# 05-Front_Panel_SFP.net
KiCad netlist of a schematic drawn in Altium Designer
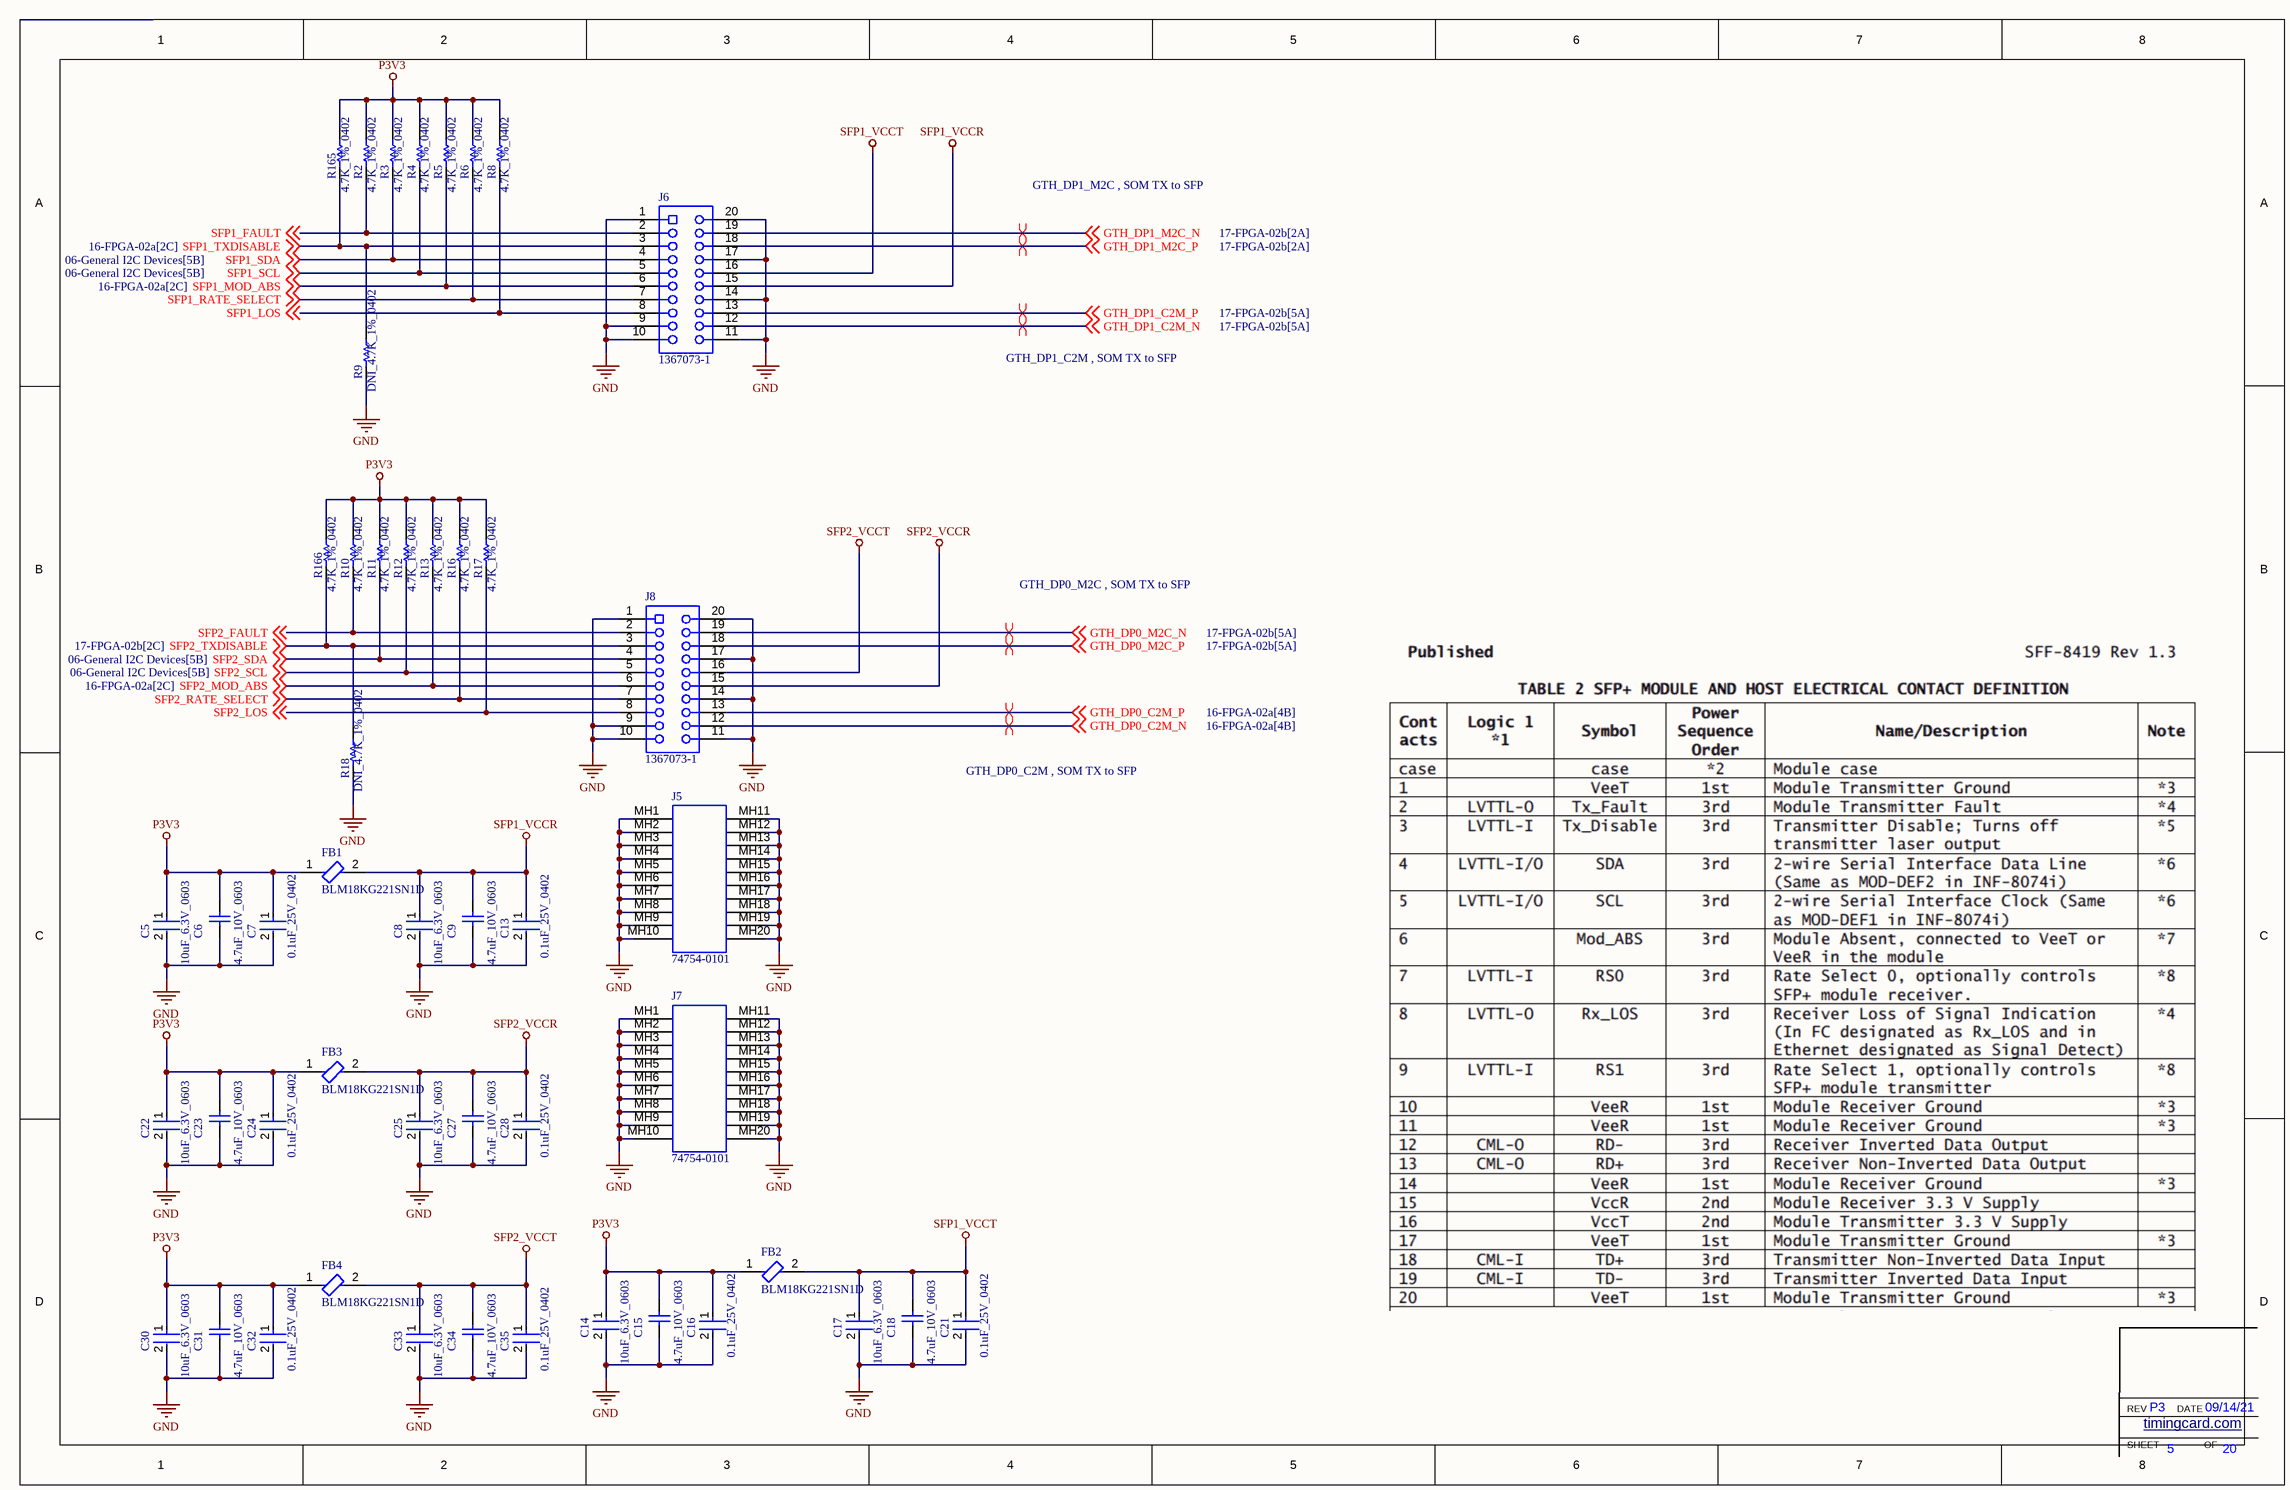
[diagram p0: 05-Front Panel SFP+.SchDoc]

(export (version "E")
  (design (tool "Eeschema 10.0.6"))
  (components
    (comp (ref "C5")
      (value "10uF_6.3V_0603")
      (footprint "FP-C0603C106M9PACTU-MFG")
      (description "CAP CER 10UF 6.3V X5R 0603")
      (fields
        (field (name "MANUFACTURER PART NUMBER") "C0603C106M9PACTU")
        (field (name "MANUFACTURER") "Kemet")
      )
      (libsource (lib "Altium Content Vault") (part "b4654b650e69147ec39a6b967a45e02"))
    )
    (comp (ref "C6")
      (value "4.7uF_10V_0603")
      (footprint "CAPC1608X87X35NL15T15")
      (fields (field (name "PART NUMBER") "C0603C475K8PACTU") (field (name "MANUFACTURER") "Kemet"))
      (libsource (lib "Altium Content Vault") (part "CAP"))
    )
    (comp (ref "C7")
      (value "0.1uF_25V_0402")
      (footprint "FP-0402-L_1_0_1-W_0_5_0_1-IPC_C")
      (description "General Purpose Ceramic Capacitor, 0402, 100nF, 10%, X7R, 15%, 25V")
      (fields (field (name "VOLTAGE") "25V") (field (name "TOLERANCE") "10%"))
      (libsource (lib "Altium Content Vault") (part "b4654b650e69147ec39a6b967a45e02"))
    )
    (comp (ref "C8")
      (value "10uF_6.3V_0603")
      (footprint "FP-C0603C106M9PACTU-MFG")
      (description "CAP CER 10UF 6.3V X5R 0603")
      (fields
        (field (name "MANUFACTURER PART NUMBER") "C0603C106M9PACTU")
        (field (name "MANUFACTURER") "Kemet")
      )
      (libsource (lib "Altium Content Vault") (part "b4654b650e69147ec39a6b967a45e02"))
    )
    (comp (ref "C9")
      (value "4.7uF_10V_0603")
      (footprint "CAPC1608X87X35NL15T15")
      (fields (field (name "PART NUMBER") "C0603C475K8PACTU") (field (name "MANUFACTURER") "Kemet"))
      (libsource (lib "Altium Content Vault") (part "CAP"))
    )
    (comp (ref "C13")
      (value "0.1uF_25V_0402")
      (footprint "FP-0402-L_1_0_1-W_0_5_0_1-IPC_C")
      (description "General Purpose Ceramic Capacitor, 0402, 100nF, 10%, X7R, 15%, 25V")
      (fields (field (name "VOLTAGE") "25V") (field (name "TOLERANCE") "10%"))
      (libsource (lib "Altium Content Vault") (part "b4654b650e69147ec39a6b967a45e02"))
    )
    (comp (ref "C14")
      (value "10uF_6.3V_0603")
      (footprint "FP-C0603C106M9PACTU-MFG")
      (description "CAP CER 10UF 6.3V X5R 0603")
      (fields
        (field (name "MANUFACTURER PART NUMBER") "C0603C106M9PACTU")
        (field (name "MANUFACTURER") "Kemet")
      )
      (libsource (lib "Altium Content Vault") (part "b4654b650e69147ec39a6b967a45e02"))
    )
    (comp (ref "C15")
      (value "4.7uF_10V_0603")
      (footprint "CAPC1608X87X35NL15T15")
      (fields (field (name "PART NUMBER") "C0603C475K8PACTU") (field (name "MANUFACTURER") "Kemet"))
      (libsource (lib "Altium Content Vault") (part "CAP"))
    )
    (comp (ref "C16")
      (value "0.1uF_25V_0402")
      (footprint "FP-0402-L_1_0_1-W_0_5_0_1-IPC_C")
      (description "General Purpose Ceramic Capacitor, 0402, 100nF, 10%, X7R, 15%, 25V")
      (fields (field (name "VOLTAGE") "25V") (field (name "TOLERANCE") "10%"))
      (libsource (lib "Altium Content Vault") (part "b4654b650e69147ec39a6b967a45e02"))
    )
    (comp (ref "C17")
      (value "10uF_6.3V_0603")
      (footprint "FP-C0603C106M9PACTU-MFG")
      (description "CAP CER 10UF 6.3V X5R 0603")
      (fields
        (field (name "MANUFACTURER PART NUMBER") "C0603C106M9PACTU")
        (field (name "MANUFACTURER") "Kemet")
      )
      (libsource (lib "Altium Content Vault") (part "b4654b650e69147ec39a6b967a45e02"))
    )
    (comp (ref "C18")
      (value "4.7uF_10V_0603")
      (footprint "CAPC1608X87X35NL15T15")
      (fields (field (name "PART NUMBER") "C0603C475K8PACTU") (field (name "MANUFACTURER") "Kemet"))
      (libsource (lib "Altium Content Vault") (part "CAP"))
    )
    (comp (ref "C21")
      (value "0.1uF_25V_0402")
      (footprint "FP-0402-L_1_0_1-W_0_5_0_1-IPC_C")
      (description "General Purpose Ceramic Capacitor, 0402, 100nF, 10%, X7R, 15%, 25V")
      (fields (field (name "VOLTAGE") "25V") (field (name "TOLERANCE") "10%"))
      (libsource (lib "Altium Content Vault") (part "b4654b650e69147ec39a6b967a45e02"))
    )
    (comp (ref "C22")
      (value "10uF_6.3V_0603")
      (footprint "FP-C0603C106M9PACTU-MFG")
      (description "CAP CER 10UF 6.3V X5R 0603")
      (fields
        (field (name "MANUFACTURER PART NUMBER") "C0603C106M9PACTU")
        (field (name "MANUFACTURER") "Kemet")
      )
      (libsource (lib "Altium Content Vault") (part "b4654b650e69147ec39a6b967a45e02"))
    )
    (comp (ref "C23")
      (value "4.7uF_10V_0603")
      (footprint "CAPC1608X87X35NL15T15")
      (fields (field (name "PART NUMBER") "C0603C475K8PACTU") (field (name "MANUFACTURER") "Kemet"))
      (libsource (lib "Altium Content Vault") (part "CAP"))
    )
    (comp (ref "C24")
      (value "0.1uF_25V_0402")
      (footprint "FP-0402-L_1_0_1-W_0_5_0_1-IPC_C")
      (description "General Purpose Ceramic Capacitor, 0402, 100nF, 10%, X7R, 15%, 25V")
      (fields (field (name "VOLTAGE") "25V") (field (name "TOLERANCE") "10%"))
      (libsource (lib "Altium Content Vault") (part "b4654b650e69147ec39a6b967a45e02"))
    )
    (comp (ref "C25")
      (value "10uF_6.3V_0603")
      (footprint "FP-C0603C106M9PACTU-MFG")
      (description "CAP CER 10UF 6.3V X5R 0603")
      (fields
        (field (name "MANUFACTURER PART NUMBER") "C0603C106M9PACTU")
        (field (name "MANUFACTURER") "Kemet")
      )
      (libsource (lib "Altium Content Vault") (part "b4654b650e69147ec39a6b967a45e02"))
    )
    (comp (ref "C27")
      (value "4.7uF_10V_0603")
      (footprint "CAPC1608X87X35NL15T15")
      (fields (field (name "PART NUMBER") "C0603C475K8PACTU") (field (name "MANUFACTURER") "Kemet"))
      (libsource (lib "Altium Content Vault") (part "CAP"))
    )
    (comp (ref "C28")
      (value "0.1uF_25V_0402")
      (footprint "FP-0402-L_1_0_1-W_0_5_0_1-IPC_C")
      (description "General Purpose Ceramic Capacitor, 0402, 100nF, 10%, X7R, 15%, 25V")
      (fields (field (name "VOLTAGE") "25V") (field (name "TOLERANCE") "10%"))
      (libsource (lib "Altium Content Vault") (part "b4654b650e69147ec39a6b967a45e02"))
    )
    (comp (ref "C30")
      (value "10uF_6.3V_0603")
      (footprint "FP-C0603C106M9PACTU-MFG")
      (description "CAP CER 10UF 6.3V X5R 0603")
      (fields
        (field (name "MANUFACTURER PART NUMBER") "C0603C106M9PACTU")
        (field (name "MANUFACTURER") "Kemet")
      )
      (libsource (lib "Altium Content Vault") (part "b4654b650e69147ec39a6b967a45e02"))
    )
    (comp (ref "C31")
      (value "4.7uF_10V_0603")
      (footprint "CAPC1608X87X35NL15T15")
      (fields (field (name "PART NUMBER") "C0603C475K8PACTU") (field (name "MANUFACTURER") "Kemet"))
      (libsource (lib "Altium Content Vault") (part "CAP"))
    )
    (comp (ref "C32")
      (value "0.1uF_25V_0402")
      (footprint "FP-0402-L_1_0_1-W_0_5_0_1-IPC_C")
      (description "General Purpose Ceramic Capacitor, 0402, 100nF, 10%, X7R, 15%, 25V")
      (fields (field (name "VOLTAGE") "25V") (field (name "TOLERANCE") "10%"))
      (libsource (lib "Altium Content Vault") (part "b4654b650e69147ec39a6b967a45e02"))
    )
    (comp (ref "C33")
      (value "10uF_6.3V_0603")
      (footprint "FP-C0603C106M9PACTU-MFG")
      (description "CAP CER 10UF 6.3V X5R 0603")
      (fields
        (field (name "MANUFACTURER PART NUMBER") "C0603C106M9PACTU")
        (field (name "MANUFACTURER") "Kemet")
      )
      (libsource (lib "Altium Content Vault") (part "b4654b650e69147ec39a6b967a45e02"))
    )
    (comp (ref "C34")
      (value "4.7uF_10V_0603")
      (footprint "CAPC1608X87X35NL15T15")
      (fields (field (name "PART NUMBER") "C0603C475K8PACTU") (field (name "MANUFACTURER") "Kemet"))
      (libsource (lib "Altium Content Vault") (part "CAP"))
    )
    (comp (ref "C35")
      (value "0.1uF_25V_0402")
      (footprint "FP-0402-L_1_0_1-W_0_5_0_1-IPC_C")
      (description "General Purpose Ceramic Capacitor, 0402, 100nF, 10%, X7R, 15%, 25V")
      (fields (field (name "VOLTAGE") "25V") (field (name "TOLERANCE") "10%"))
      (libsource (lib "Altium Content Vault") (part "b4654b650e69147ec39a6b967a45e02"))
    )
    (comp (ref "FB1")
      (value "BLM18KG221SN1D")
      (footprint "FP-BLM18-0_15-t0_8-IPC_B")
      (description "Chip Ferrite Bead, 0603, 220Ω @ 100MHz, 0.05Ω, 25%, 2.2A")
      (fields (field (name "TOLERANCE") "25%"))
      (libsource (lib "Altium Content Vault") (part "5f30dd21d616792df468990f7003faa"))
    )
    (comp (ref "FB2")
      (value "BLM18KG221SN1D")
      (footprint "FP-BLM18-0_15-t0_8-IPC_B")
      (description "Chip Ferrite Bead, 0603, 220Ω @ 100MHz, 0.05Ω, 25%, 2.2A")
      (fields (field (name "TOLERANCE") "25%"))
      (libsource (lib "Altium Content Vault") (part "5f30dd21d616792df468990f7003faa"))
    )
    (comp (ref "FB3")
      (value "BLM18KG221SN1D")
      (footprint "FP-BLM18-0_15-t0_8-IPC_B")
      (description "Chip Ferrite Bead, 0603, 220Ω @ 100MHz, 0.05Ω, 25%, 2.2A")
      (fields (field (name "TOLERANCE") "25%"))
      (libsource (lib "Altium Content Vault") (part "5f30dd21d616792df468990f7003faa"))
    )
    (comp (ref "FB4")
      (value "BLM18KG221SN1D")
      (footprint "FP-BLM18-0_15-t0_8-IPC_B")
      (description "Chip Ferrite Bead, 0603, 220Ω @ 100MHz, 0.05Ω, 25%, 2.2A")
      (fields (field (name "TOLERANCE") "25%"))
      (libsource (lib "Altium Content Vault") (part "5f30dd21d616792df468990f7003faa"))
    )
    (comp (ref "J5")
      (value "74754-0101")
      (footprint "MOLX-74754-0101_V")
      (description "SFP+ Cage, Single Port, Height 10.85 mm, Tail Height 3.05 mm, -40 to 85 degC, RoHS, Tray")
      (libsource (lib "Altium Content Vault") (part "MOLX-74754-0101"))
    )
    (comp (ref "J6")
      (value "1367073-1")
      (footprint "TECO-1367073-1_V")
      (fields (field (name "MANUFACTURER") "TE Connectivity"))
      (libsource (lib "Altium Content Vault") (part "CN-2P-F-R20_B"))
    )
    (comp (ref "J7")
      (value "74754-0101")
      (footprint "MOLX-74754-0101_V")
      (description "SFP+ Cage, Single Port, Height 10.85 mm, Tail Height 3.05 mm, -40 to 85 degC, RoHS, Tray")
      (libsource (lib "Altium Content Vault") (part "MOLX-74754-0101"))
    )
    (comp (ref "J8")
      (value "1367073-1")
      (footprint "TECO-1367073-1_V")
      (fields (field (name "MANUFACTURER") "TE Connectivity"))
      (libsource (lib "Altium Content Vault") (part "CN-2P-F-R20_B"))
    )
    (comp (ref "R2")
      (value "4.7K_1%_0402")
      (footprint "RESC1005X40X25NL10T10")
      (fields (field (name "MANUFACTURER") "Bourns") (field (name "PART NUMBER") "CR0402-FX-4701GLF"))
      (libsource (lib "Altium Content Vault") (part "RES"))
    )
    (comp (ref "R3")
      (value "4.7K_1%_0402")
      (footprint "RESC1005X40X25NL10T10")
      (fields (field (name "MANUFACTURER") "Bourns") (field (name "PART NUMBER") "CR0402-FX-4701GLF"))
      (libsource (lib "Altium Content Vault") (part "RES"))
    )
    (comp (ref "R4")
      (value "4.7K_1%_0402")
      (footprint "RESC1005X40X25NL10T10")
      (fields (field (name "MANUFACTURER") "Bourns") (field (name "PART NUMBER") "CR0402-FX-4701GLF"))
      (libsource (lib "Altium Content Vault") (part "RES"))
    )
    (comp (ref "R5")
      (value "4.7K_1%_0402")
      (footprint "RESC1005X40X25NL10T10")
      (fields (field (name "MANUFACTURER") "Bourns") (field (name "PART NUMBER") "CR0402-FX-4701GLF"))
      (libsource (lib "Altium Content Vault") (part "RES"))
    )
    (comp (ref "R6")
      (value "4.7K_1%_0402")
      (footprint "RESC1005X40X25NL10T10")
      (fields (field (name "MANUFACTURER") "Bourns") (field (name "PART NUMBER") "CR0402-FX-4701GLF"))
      (libsource (lib "Altium Content Vault") (part "RES"))
    )
    (comp (ref "R8")
      (value "4.7K_1%_0402")
      (footprint "RESC1005X40X25NL10T10")
      (fields (field (name "MANUFACTURER") "Bourns") (field (name "PART NUMBER") "CR0402-FX-4701GLF"))
      (libsource (lib "Altium Content Vault") (part "RES"))
    )
    (comp (ref "R9")
      (value "DNI_4.7K_1%_0402")
      (footprint "RESC1005X40X25NL10T10")
      (fields (field (name "MANUFACTURER") "Bourns") (field (name "PART NUMBER") "CR0402-FX-4701GLF"))
      (libsource (lib "Altium Content Vault") (part "RES"))
    )
    (comp (ref "R10")
      (value "4.7K_1%_0402")
      (footprint "RESC1005X40X25NL10T10")
      (fields (field (name "MANUFACTURER") "Bourns") (field (name "PART NUMBER") "CR0402-FX-4701GLF"))
      (libsource (lib "Altium Content Vault") (part "RES"))
    )
    (comp (ref "R11")
      (value "4.7K_1%_0402")
      (footprint "RESC1005X40X25NL10T10")
      (fields (field (name "MANUFACTURER") "Bourns") (field (name "PART NUMBER") "CR0402-FX-4701GLF"))
      (libsource (lib "Altium Content Vault") (part "RES"))
    )
    (comp (ref "R12")
      (value "4.7K_1%_0402")
      (footprint "RESC1005X40X25NL10T10")
      (fields (field (name "MANUFACTURER") "Bourns") (field (name "PART NUMBER") "CR0402-FX-4701GLF"))
      (libsource (lib "Altium Content Vault") (part "RES"))
    )
    (comp (ref "R13")
      (value "4.7K_1%_0402")
      (footprint "RESC1005X40X25NL10T10")
      (fields (field (name "MANUFACTURER") "Bourns") (field (name "PART NUMBER") "CR0402-FX-4701GLF"))
      (libsource (lib "Altium Content Vault") (part "RES"))
    )
    (comp (ref "R16")
      (value "4.7K_1%_0402")
      (footprint "RESC1005X40X25NL10T10")
      (fields (field (name "MANUFACTURER") "Bourns") (field (name "PART NUMBER") "CR0402-FX-4701GLF"))
      (libsource (lib "Altium Content Vault") (part "RES"))
    )
    (comp (ref "R17")
      (value "4.7K_1%_0402")
      (footprint "RESC1005X40X25NL10T10")
      (fields (field (name "MANUFACTURER") "Bourns") (field (name "PART NUMBER") "CR0402-FX-4701GLF"))
      (libsource (lib "Altium Content Vault") (part "RES"))
    )
    (comp (ref "R18")
      (value "DNI_4.7K_1%_0402")
      (footprint "RESC1005X40X25NL10T10")
      (fields (field (name "MANUFACTURER") "Bourns") (field (name "PART NUMBER") "CR0402-FX-4701GLF"))
      (libsource (lib "Altium Content Vault") (part "RES"))
    )
    (comp (ref "R165")
      (value "4.7K_1%_0402")
      (footprint "RESC1005X40X25NL10T10")
      (fields (field (name "MANUFACTURER") "Bourns") (field (name "PART NUMBER") "CR0402-FX-4701GLF"))
      (libsource (lib "Altium Content Vault") (part "RES"))
    )
    (comp (ref "R166")
      (value "4.7K_1%_0402")
      (footprint "RESC1005X40X25NL10T10")
      (fields (field (name "MANUFACTURER") "Bourns") (field (name "PART NUMBER") "CR0402-FX-4701GLF"))
      (libsource (lib "Altium Content Vault") (part "RES"))
    )
  )
  (nets
    (net (code "1") (name "GND") (class "Default")
      (node (ref "C13") (pin "2") (pinfunction "2_2") (pintype "passive"))
      (node (ref "C14") (pin "2") (pinfunction "2_2") (pintype "passive"))
      (node (ref "C15") (pin "1") (pinfunction "1_1") (pintype "passive"))
      (node (ref "C16") (pin "2") (pinfunction "2_2") (pintype "passive"))
      (node (ref "C17") (pin "2") (pinfunction "2_2") (pintype "passive"))
      (node (ref "C18") (pin "1") (pinfunction "1_1") (pintype "passive"))
      (node (ref "C21") (pin "2") (pinfunction "2_2") (pintype "passive"))
      (node (ref "C22") (pin "2") (pinfunction "2_2") (pintype "passive"))
      (node (ref "C23") (pin "1") (pinfunction "1_1") (pintype "passive"))
      (node (ref "C24") (pin "2") (pinfunction "2_2") (pintype "passive"))
      (node (ref "C25") (pin "2") (pinfunction "2_2") (pintype "passive"))
      (node (ref "C27") (pin "1") (pinfunction "1_1") (pintype "passive"))
      (node (ref "C28") (pin "2") (pinfunction "2_2") (pintype "passive"))
      (node (ref "C30") (pin "2") (pinfunction "2_2") (pintype "passive"))
      (node (ref "C31") (pin "1") (pinfunction "1_1") (pintype "passive"))
      (node (ref "C32") (pin "2") (pinfunction "2_2") (pintype "passive"))
      (node (ref "C33") (pin "2") (pinfunction "2_2") (pintype "passive"))
      (node (ref "C34") (pin "1") (pinfunction "1_1") (pintype "passive"))
      (node (ref "C35") (pin "2") (pinfunction "2_2") (pintype "passive"))
      (node (ref "C5") (pin "2") (pinfunction "2_2") (pintype "passive"))
      (node (ref "C6") (pin "1") (pinfunction "1_1") (pintype "passive"))
      (node (ref "C7") (pin "2") (pinfunction "2_2") (pintype "passive"))
      (node (ref "C8") (pin "2") (pinfunction "2_2") (pintype "passive"))
      (node (ref "C9") (pin "1") (pinfunction "1_1") (pintype "passive"))
      (node (ref "J5") (pin "MH1") (pinfunction "MH1_MH1") (pintype "passive"))
      (node (ref "J5") (pin "MH10") (pinfunction "MH10_MH10") (pintype "passive"))
      (node (ref "J5") (pin "MH11") (pinfunction "MH11_MH11") (pintype "passive"))
      (node (ref "J5") (pin "MH12") (pinfunction "MH12_MH12") (pintype "passive"))
      (node (ref "J5") (pin "MH13") (pinfunction "MH13_MH13") (pintype "passive"))
      (node (ref "J5") (pin "MH14") (pinfunction "MH14_MH14") (pintype "passive"))
      (node (ref "J5") (pin "MH15") (pinfunction "MH15_MH15") (pintype "passive"))
      (node (ref "J5") (pin "MH16") (pinfunction "MH16_MH16") (pintype "passive"))
      (node (ref "J5") (pin "MH17") (pinfunction "MH17_MH17") (pintype "passive"))
      (node (ref "J5") (pin "MH18") (pinfunction "MH18_MH18") (pintype "passive"))
      (node (ref "J5") (pin "MH19") (pinfunction "MH19_MH19") (pintype "passive"))
      (node (ref "J5") (pin "MH2") (pinfunction "MH2_MH2") (pintype "passive"))
      (node (ref "J5") (pin "MH20") (pinfunction "MH20_MH20") (pintype "passive"))
      (node (ref "J5") (pin "MH3") (pinfunction "MH3_MH3") (pintype "passive"))
      (node (ref "J5") (pin "MH4") (pinfunction "MH4_MH4") (pintype "passive"))
      (node (ref "J5") (pin "MH5") (pinfunction "MH5_MH5") (pintype "passive"))
      (node (ref "J5") (pin "MH6") (pinfunction "MH6_MH6") (pintype "passive"))
      (node (ref "J5") (pin "MH7") (pinfunction "MH7_MH7") (pintype "passive"))
      (node (ref "J5") (pin "MH8") (pinfunction "MH8_MH8") (pintype "passive"))
      (node (ref "J5") (pin "MH9") (pinfunction "MH9_MH9") (pintype "passive"))
      (node (ref "J6") (pin "1") (pinfunction "1_1") (pintype "passive"))
      (node (ref "J6") (pin "10") (pinfunction "10_10") (pintype "passive"))
      (node (ref "J6") (pin "11") (pinfunction "11_11") (pintype "passive"))
      (node (ref "J6") (pin "14") (pinfunction "14_14") (pintype "passive"))
      (node (ref "J6") (pin "17") (pinfunction "17_17") (pintype "passive"))
      (node (ref "J6") (pin "20") (pinfunction "20_20") (pintype "passive"))
      (node (ref "J6") (pin "9") (pinfunction "9_9") (pintype "passive"))
      (node (ref "J7") (pin "MH1") (pinfunction "MH1_MH1") (pintype "passive"))
      (node (ref "J7") (pin "MH10") (pinfunction "MH10_MH10") (pintype "passive"))
      (node (ref "J7") (pin "MH11") (pinfunction "MH11_MH11") (pintype "passive"))
      (node (ref "J7") (pin "MH12") (pinfunction "MH12_MH12") (pintype "passive"))
      (node (ref "J7") (pin "MH13") (pinfunction "MH13_MH13") (pintype "passive"))
      (node (ref "J7") (pin "MH14") (pinfunction "MH14_MH14") (pintype "passive"))
      (node (ref "J7") (pin "MH15") (pinfunction "MH15_MH15") (pintype "passive"))
      (node (ref "J7") (pin "MH16") (pinfunction "MH16_MH16") (pintype "passive"))
      (node (ref "J7") (pin "MH17") (pinfunction "MH17_MH17") (pintype "passive"))
      (node (ref "J7") (pin "MH18") (pinfunction "MH18_MH18") (pintype "passive"))
      (node (ref "J7") (pin "MH19") (pinfunction "MH19_MH19") (pintype "passive"))
      (node (ref "J7") (pin "MH2") (pinfunction "MH2_MH2") (pintype "passive"))
      (node (ref "J7") (pin "MH20") (pinfunction "MH20_MH20") (pintype "passive"))
      (node (ref "J7") (pin "MH3") (pinfunction "MH3_MH3") (pintype "passive"))
      (node (ref "J7") (pin "MH4") (pinfunction "MH4_MH4") (pintype "passive"))
      (node (ref "J7") (pin "MH5") (pinfunction "MH5_MH5") (pintype "passive"))
      (node (ref "J7") (pin "MH6") (pinfunction "MH6_MH6") (pintype "passive"))
      (node (ref "J7") (pin "MH7") (pinfunction "MH7_MH7") (pintype "passive"))
      (node (ref "J7") (pin "MH8") (pinfunction "MH8_MH8") (pintype "passive"))
      (node (ref "J7") (pin "MH9") (pinfunction "MH9_MH9") (pintype "passive"))
      (node (ref "J8") (pin "1") (pinfunction "1_1") (pintype "passive"))
      (node (ref "J8") (pin "10") (pinfunction "10_10") (pintype "passive"))
      (node (ref "J8") (pin "11") (pinfunction "11_11") (pintype "passive"))
      (node (ref "J8") (pin "14") (pinfunction "14_14") (pintype "passive"))
      (node (ref "J8") (pin "17") (pinfunction "17_17") (pintype "passive"))
      (node (ref "J8") (pin "20") (pinfunction "20_20") (pintype "passive"))
      (node (ref "J8") (pin "9") (pinfunction "9_9") (pintype "passive"))
      (node (ref "R18") (pin "2") (pinfunction "2_2") (pintype "passive"))
      (node (ref "R9") (pin "2") (pinfunction "2_2") (pintype "passive"))
    )
    (net (code "2") (name "GTH_DP0_C2M_N") (class "Default")
      (node (ref "J8") (pin "12") (pinfunction "12_12") (pintype "passive"))
    )
    (net (code "3") (name "GTH_DP0_C2M_P") (class "Default")
      (node (ref "J8") (pin "13") (pinfunction "13_13") (pintype "passive"))
    )
    (net (code "4") (name "GTH_DP0_M2C_N") (class "Default")
      (node (ref "J8") (pin "19") (pinfunction "19_19") (pintype "passive"))
    )
    (net (code "5") (name "GTH_DP0_M2C_P") (class "Default")
      (node (ref "J8") (pin "18") (pinfunction "18_18") (pintype "passive"))
    )
    (net (code "6") (name "GTH_DP1_C2M_N") (class "Default")
      (node (ref "J6") (pin "12") (pinfunction "12_12") (pintype "passive"))
    )
    (net (code "7") (name "GTH_DP1_C2M_P") (class "Default")
      (node (ref "J6") (pin "13") (pinfunction "13_13") (pintype "passive"))
    )
    (net (code "8") (name "GTH_DP1_M2C_N") (class "Default")
      (node (ref "J6") (pin "19") (pinfunction "19_19") (pintype "passive"))
    )
    (net (code "9") (name "GTH_DP1_M2C_P") (class "Default")
      (node (ref "J6") (pin "18") (pinfunction "18_18") (pintype "passive"))
    )
    (net (code "10") (name "P3V3") (class "Default")
      (node (ref "C14") (pin "1") (pinfunction "1_1") (pintype "passive"))
      (node (ref "C15") (pin "2") (pinfunction "2_2") (pintype "passive"))
      (node (ref "C16") (pin "1") (pinfunction "1_1") (pintype "passive"))
      (node (ref "C22") (pin "1") (pinfunction "1_1") (pintype "passive"))
      (node (ref "C23") (pin "2") (pinfunction "2_2") (pintype "passive"))
      (node (ref "C24") (pin "1") (pinfunction "1_1") (pintype "passive"))
      (node (ref "C30") (pin "1") (pinfunction "1_1") (pintype "passive"))
      (node (ref "C31") (pin "2") (pinfunction "2_2") (pintype "passive"))
      (node (ref "C32") (pin "1") (pinfunction "1_1") (pintype "passive"))
      (node (ref "C5") (pin "1") (pinfunction "1_1") (pintype "passive"))
      (node (ref "C6") (pin "2") (pinfunction "2_2") (pintype "passive"))
      (node (ref "C7") (pin "1") (pinfunction "1_1") (pintype "passive"))
      (node (ref "FB1") (pin "1") (pinfunction "1_1") (pintype "passive"))
      (node (ref "FB2") (pin "1") (pinfunction "1_1") (pintype "passive"))
      (node (ref "FB3") (pin "1") (pinfunction "1_1") (pintype "passive"))
      (node (ref "FB4") (pin "1") (pinfunction "1_1") (pintype "passive"))
      (node (ref "R10") (pin "1") (pinfunction "1_1") (pintype "passive"))
      (node (ref "R11") (pin "1") (pinfunction "1_1") (pintype "passive"))
      (node (ref "R12") (pin "1") (pinfunction "1_1") (pintype "passive"))
      (node (ref "R13") (pin "1") (pinfunction "1_1") (pintype "passive"))
      (node (ref "R16") (pin "1") (pinfunction "1_1") (pintype "passive"))
      (node (ref "R165") (pin "1") (pinfunction "1_1") (pintype "passive"))
      (node (ref "R166") (pin "1") (pinfunction "1_1") (pintype "passive"))
      (node (ref "R17") (pin "1") (pinfunction "1_1") (pintype "passive"))
      (node (ref "R2") (pin "1") (pinfunction "1_1") (pintype "passive"))
      (node (ref "R3") (pin "1") (pinfunction "1_1") (pintype "passive"))
      (node (ref "R4") (pin "1") (pinfunction "1_1") (pintype "passive"))
      (node (ref "R5") (pin "1") (pinfunction "1_1") (pintype "passive"))
      (node (ref "R6") (pin "1") (pinfunction "1_1") (pintype "passive"))
      (node (ref "R8") (pin "1") (pinfunction "1_1") (pintype "passive"))
    )
    (net (code "11") (name "SFP1_FAULT") (class "Default")
      (node (ref "J6") (pin "2") (pinfunction "2_2") (pintype "passive"))
      (node (ref "R2") (pin "2") (pinfunction "2_2") (pintype "passive"))
    )
    (net (code "12") (name "SFP1_LOS") (class "Default")
      (node (ref "J6") (pin "8") (pinfunction "8_8") (pintype "passive"))
      (node (ref "R8") (pin "2") (pinfunction "2_2") (pintype "passive"))
    )
    (net (code "13") (name "SFP1_MOD_ABS") (class "Default")
      (node (ref "J6") (pin "6") (pinfunction "6_6") (pintype "passive"))
      (node (ref "R5") (pin "2") (pinfunction "2_2") (pintype "passive"))
    )
    (net (code "14") (name "SFP1_RATE_SELECT") (class "Default")
      (node (ref "J6") (pin "7") (pinfunction "7_7") (pintype "passive"))
      (node (ref "R6") (pin "2") (pinfunction "2_2") (pintype "passive"))
    )
    (net (code "15") (name "SFP1_SCL") (class "Default")
      (node (ref "J6") (pin "5") (pinfunction "5_5") (pintype "passive"))
      (node (ref "R4") (pin "2") (pinfunction "2_2") (pintype "passive"))
    )
    (net (code "16") (name "SFP1_SDA") (class "Default")
      (node (ref "J6") (pin "4") (pinfunction "4_4") (pintype "passive"))
      (node (ref "R3") (pin "2") (pinfunction "2_2") (pintype "passive"))
    )
    (net (code "17") (name "SFP1_TXDISABLE") (class "Default")
      (node (ref "J6") (pin "3") (pinfunction "3_3") (pintype "passive"))
      (node (ref "R165") (pin "2") (pinfunction "2_2") (pintype "passive"))
      (node (ref "R9") (pin "1") (pinfunction "1_1") (pintype "passive"))
    )
    (net (code "18") (name "SFP1_VCCR") (class "Default")
      (node (ref "C13") (pin "1") (pinfunction "1_1") (pintype "passive"))
      (node (ref "C8") (pin "1") (pinfunction "1_1") (pintype "passive"))
      (node (ref "C9") (pin "2") (pinfunction "2_2") (pintype "passive"))
      (node (ref "FB1") (pin "2") (pinfunction "2_2") (pintype "passive"))
      (node (ref "J6") (pin "15") (pinfunction "15_15") (pintype "passive"))
    )
    (net (code "19") (name "SFP1_VCCT") (class "Default")
      (node (ref "C17") (pin "1") (pinfunction "1_1") (pintype "passive"))
      (node (ref "C18") (pin "2") (pinfunction "2_2") (pintype "passive"))
      (node (ref "C21") (pin "1") (pinfunction "1_1") (pintype "passive"))
      (node (ref "FB2") (pin "2") (pinfunction "2_2") (pintype "passive"))
      (node (ref "J6") (pin "16") (pinfunction "16_16") (pintype "passive"))
    )
    (net (code "20") (name "SFP2_FAULT") (class "Default")
      (node (ref "J8") (pin "2") (pinfunction "2_2") (pintype "passive"))
      (node (ref "R10") (pin "2") (pinfunction "2_2") (pintype "passive"))
    )
    (net (code "21") (name "SFP2_LOS") (class "Default")
      (node (ref "J8") (pin "8") (pinfunction "8_8") (pintype "passive"))
      (node (ref "R17") (pin "2") (pinfunction "2_2") (pintype "passive"))
    )
    (net (code "22") (name "SFP2_MOD_ABS") (class "Default")
      (node (ref "J8") (pin "6") (pinfunction "6_6") (pintype "passive"))
      (node (ref "R13") (pin "2") (pinfunction "2_2") (pintype "passive"))
    )
    (net (code "23") (name "SFP2_RATE_SELECT") (class "Default")
      (node (ref "J8") (pin "7") (pinfunction "7_7") (pintype "passive"))
      (node (ref "R16") (pin "2") (pinfunction "2_2") (pintype "passive"))
    )
    (net (code "24") (name "SFP2_SCL") (class "Default")
      (node (ref "J8") (pin "5") (pinfunction "5_5") (pintype "passive"))
      (node (ref "R12") (pin "2") (pinfunction "2_2") (pintype "passive"))
    )
    (net (code "25") (name "SFP2_SDA") (class "Default")
      (node (ref "J8") (pin "4") (pinfunction "4_4") (pintype "passive"))
      (node (ref "R11") (pin "2") (pinfunction "2_2") (pintype "passive"))
    )
    (net (code "26") (name "SFP2_TXDISABLE") (class "Default")
      (node (ref "J8") (pin "3") (pinfunction "3_3") (pintype "passive"))
      (node (ref "R166") (pin "2") (pinfunction "2_2") (pintype "passive"))
      (node (ref "R18") (pin "1") (pinfunction "1_1") (pintype "passive"))
    )
    (net (code "27") (name "SFP2_VCCR") (class "Default")
      (node (ref "C25") (pin "1") (pinfunction "1_1") (pintype "passive"))
      (node (ref "C27") (pin "2") (pinfunction "2_2") (pintype "passive"))
      (node (ref "C28") (pin "1") (pinfunction "1_1") (pintype "passive"))
      (node (ref "FB3") (pin "2") (pinfunction "2_2") (pintype "passive"))
      (node (ref "J8") (pin "15") (pinfunction "15_15") (pintype "passive"))
    )
    (net (code "28") (name "SFP2_VCCT") (class "Default")
      (node (ref "C33") (pin "1") (pinfunction "1_1") (pintype "passive"))
      (node (ref "C34") (pin "2") (pinfunction "2_2") (pintype "passive"))
      (node (ref "C35") (pin "1") (pinfunction "1_1") (pintype "passive"))
      (node (ref "FB4") (pin "2") (pinfunction "2_2") (pintype "passive"))
      (node (ref "J8") (pin "16") (pinfunction "16_16") (pintype "passive"))
    )
  )
)
